# mainboard.net
KiCad netlist of a schematic drawn in EAGLE
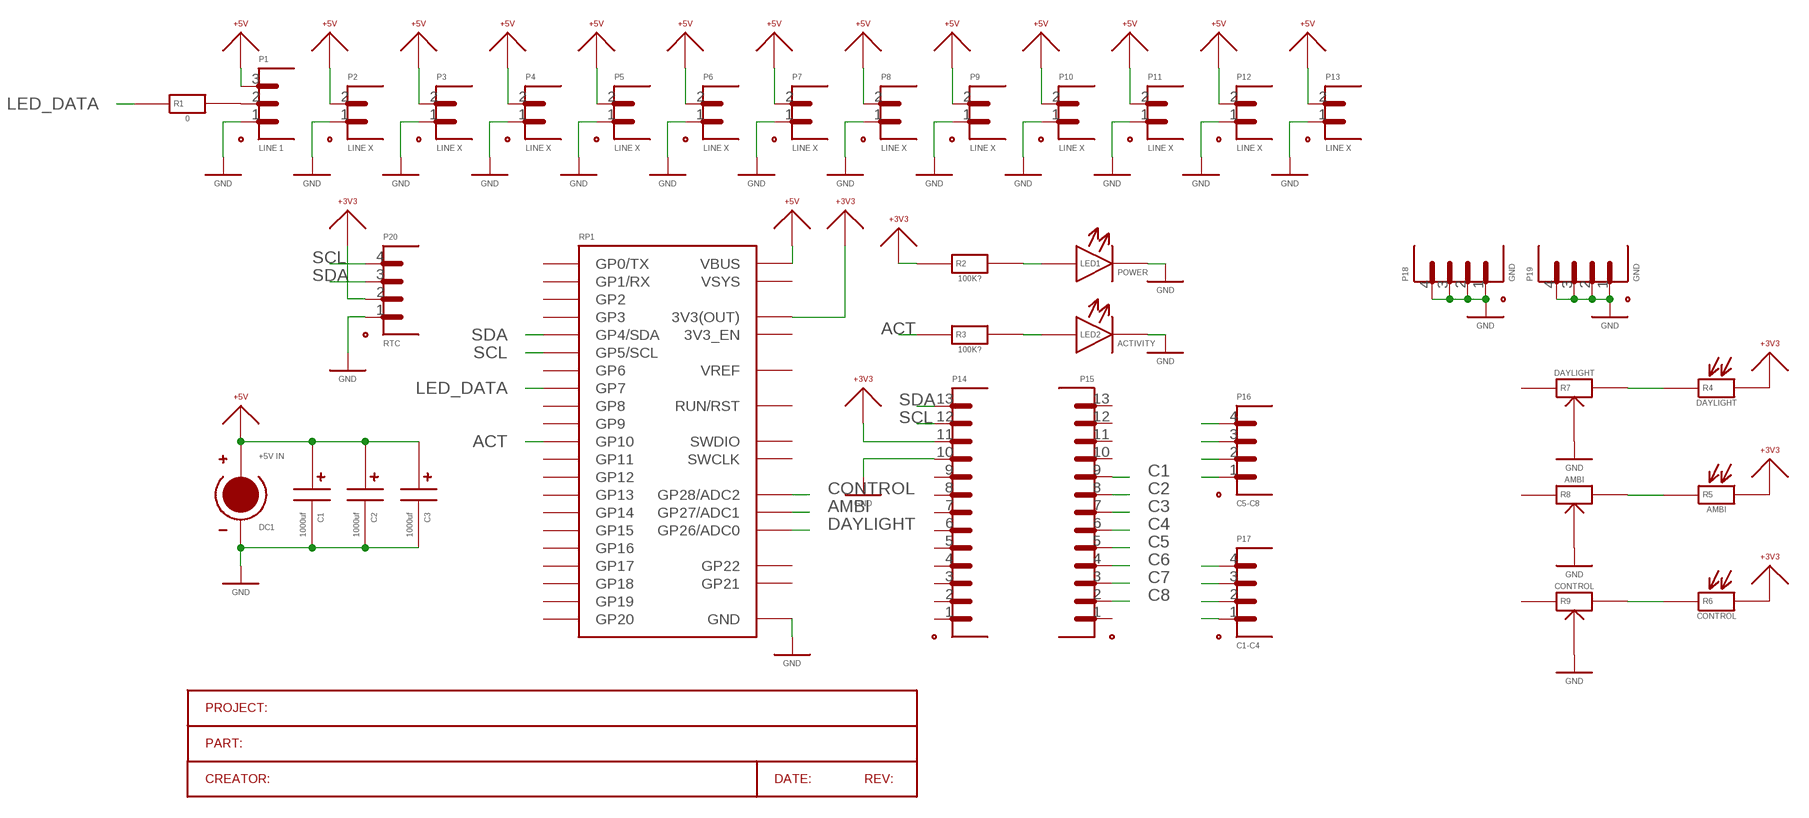
[diagram p0: schematic, sheet 1]

(export (version "E")
  (design (tool "Eeschema 10.0.6"))
  (components
    (comp (ref "C1")
      (value "1000uf")
      (footprint "eagle-import:CAPACITOR_POLAR_8MM")
      (libsource (lib "eagle-import") (part "CAPACITOR_POLARISED_8MM"))
    )
    (comp (ref "C2")
      (value "1000uf")
      (footprint "eagle-import:CAPACITOR_POLAR_8MM")
      (libsource (lib "eagle-import") (part "CAPACITOR_POLARISED_8MM"))
    )
    (comp (ref "C3")
      (value "1000uf")
      (footprint "eagle-import:CAPACITOR_POLAR_8MM")
      (libsource (lib "eagle-import") (part "CAPACITOR_POLARISED_8MM"))
    )
    (comp (ref "DC1")
      (value "+5V IN")
      (footprint "eagle-import:SCREW-TERMINAL_2-WAY")
      (libsource (lib "eagle-import") (part "DC-POWER_SCREW-TERMINAL"))
    )
    (comp (ref "LED1")
      (value "POWER")
      (footprint "eagle-import:LED_3MM")
      (libsource (lib "eagle-import") (part "LED_3MM"))
    )
    (comp (ref "LED2")
      (value "ACTIVITY")
      (footprint "eagle-import:LED_3MM")
      (libsource (lib "eagle-import") (part "LED_3MM"))
    )
    (comp (ref "P1")
      (value "LINE 1")
      (footprint "eagle-import:SCREW-TERMINAL_3-WAY")
      (libsource (lib "eagle-import") (part "PORT_3-PIN_SCREW-TERMINAL"))
    )
    (comp (ref "P2")
      (value "LINE X")
      (footprint "eagle-import:SCREW-TERMINAL_2-WAY")
      (libsource (lib "eagle-import") (part "PORT_2-PIN_SCREW-TERMINAL"))
    )
    (comp (ref "P3")
      (value "LINE X")
      (footprint "eagle-import:SCREW-TERMINAL_2-WAY")
      (libsource (lib "eagle-import") (part "PORT_2-PIN_SCREW-TERMINAL"))
    )
    (comp (ref "P4")
      (value "LINE X")
      (footprint "eagle-import:SCREW-TERMINAL_2-WAY")
      (libsource (lib "eagle-import") (part "PORT_2-PIN_SCREW-TERMINAL"))
    )
    (comp (ref "P5")
      (value "LINE X")
      (footprint "eagle-import:SCREW-TERMINAL_2-WAY")
      (libsource (lib "eagle-import") (part "PORT_2-PIN_SCREW-TERMINAL"))
    )
    (comp (ref "P6")
      (value "LINE X")
      (footprint "eagle-import:SCREW-TERMINAL_2-WAY")
      (libsource (lib "eagle-import") (part "PORT_2-PIN_SCREW-TERMINAL"))
    )
    (comp (ref "P7")
      (value "LINE X")
      (footprint "eagle-import:SCREW-TERMINAL_2-WAY")
      (libsource (lib "eagle-import") (part "PORT_2-PIN_SCREW-TERMINAL"))
    )
    (comp (ref "P8")
      (value "LINE X")
      (footprint "eagle-import:SCREW-TERMINAL_2-WAY")
      (libsource (lib "eagle-import") (part "PORT_2-PIN_SCREW-TERMINAL"))
    )
    (comp (ref "P9")
      (value "LINE X")
      (footprint "eagle-import:SCREW-TERMINAL_2-WAY")
      (libsource (lib "eagle-import") (part "PORT_2-PIN_SCREW-TERMINAL"))
    )
    (comp (ref "P10")
      (value "LINE X")
      (footprint "eagle-import:SCREW-TERMINAL_2-WAY")
      (libsource (lib "eagle-import") (part "PORT_2-PIN_SCREW-TERMINAL"))
    )
    (comp (ref "P11")
      (value "LINE X")
      (footprint "eagle-import:SCREW-TERMINAL_2-WAY")
      (libsource (lib "eagle-import") (part "PORT_2-PIN_SCREW-TERMINAL"))
    )
    (comp (ref "P12")
      (value "LINE X")
      (footprint "eagle-import:SCREW-TERMINAL_2-WAY")
      (libsource (lib "eagle-import") (part "PORT_2-PIN_SCREW-TERMINAL"))
    )
    (comp (ref "P13")
      (value "LINE X")
      (footprint "eagle-import:SCREW-TERMINAL_2-WAY")
      (libsource (lib "eagle-import") (part "PORT_2-PIN_SCREW-TERMINAL"))
    )
    (comp (ref "P14")
      (value "PORT_13-PIN_HEADER")
      (footprint "eagle-import:HEADER_13-PIN")
      (libsource (lib "eagle-import") (part "PORT_13-PIN_HEADER"))
    )
    (comp (ref "P15")
      (value "PORT_13-PIN_HEADER")
      (footprint "eagle-import:HEADER_13-PIN")
      (libsource (lib "eagle-import") (part "PORT_13-PIN_HEADER"))
    )
    (comp (ref "P16")
      (value "C5-C8")
      (footprint "eagle-import:R5210_4-PIN")
      (libsource (lib "eagle-import") (part "PORT_4-PIN_R5210"))
    )
    (comp (ref "P17")
      (value "C1-C4")
      (footprint "eagle-import:R5210_4-PIN")
      (libsource (lib "eagle-import") (part "PORT_4-PIN_R5210"))
    )
    (comp (ref "P18")
      (value "GND")
      (footprint "eagle-import:R5210_4-PIN")
      (libsource (lib "eagle-import") (part "PORT_4-PIN_R5210"))
    )
    (comp (ref "P19")
      (value "GND")
      (footprint "eagle-import:R5210_4-PIN")
      (libsource (lib "eagle-import") (part "PORT_4-PIN_R5210"))
    )
    (comp (ref "P20")
      (value "RTC")
      (footprint "eagle-import:R5210_4-PIN")
      (libsource (lib "eagle-import") (part "PORT_4-PIN_R5210"))
    )
    (comp (ref "R1")
      (value "0")
      (footprint "eagle-import:RESISTOR_10.16MM")
      (libsource (lib "eagle-import") (part "RESISTOR_10.16MM"))
    )
    (comp (ref "R2")
      (value "100K?")
      (footprint "eagle-import:RESISTOR_10.16MM")
      (libsource (lib "eagle-import") (part "RESISTOR_10.16MM"))
    )
    (comp (ref "R3")
      (value "100K?")
      (footprint "eagle-import:RESISTOR_10.16MM")
      (libsource (lib "eagle-import") (part "RESISTOR_10.16MM"))
    )
    (comp (ref "R4")
      (value "DAYLIGHT")
      (footprint "eagle-import:R5210_2-PIN")
      (libsource (lib "eagle-import") (part "RESISTOR_LRD_R5210"))
    )
    (comp (ref "R5")
      (value "AMBI")
      (footprint "eagle-import:PASSIVE_2.54MM")
      (libsource (lib "eagle-import") (part "RESISTOR_LRD_2.54MM"))
    )
    (comp (ref "R6")
      (value "CONTROL")
      (footprint "eagle-import:PASSIVE_2.54MM")
      (libsource (lib "eagle-import") (part "RESISTOR_LRD_2.54MM"))
    )
    (comp (ref "R7")
      (value "DAYLIGHT")
      (footprint "eagle-import:TRIM-POT_A")
      (libsource (lib "eagle-import") (part "RESISTOR_VARIABLE_TRIM-POT"))
    )
    (comp (ref "R8")
      (value "AMBI")
      (footprint "eagle-import:TRIM-POT_A")
      (libsource (lib "eagle-import") (part "RESISTOR_VARIABLE_TRIM-POT"))
    )
    (comp (ref "R9")
      (value "CONTROL")
      (footprint "eagle-import:TRIM-POT_A")
      (libsource (lib "eagle-import") (part "RESISTOR_VARIABLE_TRIM-POT"))
    )
    (comp (ref "RP1")
      (value "RASPBERRY-PI-PICO_W")
      (footprint "eagle-import:RASPBERRY-PI-PICO_W")
      (libsource (lib "eagle-import") (part "RASPBERRY-PI-PICO_W"))
    )
  )
  (nets
    (net (code "1") (name "+3V3") (class "Default")
      (node (ref "P14") (pin "11") (pinfunction "11_11") (pintype "bidirectional"))
      (node (ref "P20") (pin "2") (pinfunction "2_2") (pintype "bidirectional"))
      (node (ref "R2") (pin "X") (pinfunction "X_X") (pintype "passive"))
      (node (ref "R4") (pin "2") (pinfunction "Y_2") (pintype "passive"))
      (node (ref "R5") (pin "Y") (pinfunction "Y_Y") (pintype "passive"))
      (node (ref "R6") (pin "Y") (pinfunction "Y_Y") (pintype "passive"))
      (node (ref "RP1") (pin "36") (pinfunction "3V3(OUT)_36") (pintype "power_in"))
    )
    (net (code "2") (name "+5V") (class "Default")
      (node (ref "C1") (pin "A") (pinfunction "A_A") (pintype "input"))
      (node (ref "C2") (pin "A") (pinfunction "A_A") (pintype "input"))
      (node (ref "C3") (pin "A") (pinfunction "A_A") (pintype "input"))
      (node (ref "DC1") (pin "2") (pinfunction "+V_2") (pintype "power_in"))
      (node (ref "P1") (pin "3") (pinfunction "3_3") (pintype "bidirectional"))
      (node (ref "P10") (pin "2") (pinfunction "2_2") (pintype "bidirectional"))
      (node (ref "P11") (pin "2") (pinfunction "2_2") (pintype "bidirectional"))
      (node (ref "P12") (pin "2") (pinfunction "2_2") (pintype "bidirectional"))
      (node (ref "P13") (pin "2") (pinfunction "2_2") (pintype "bidirectional"))
      (node (ref "P2") (pin "2") (pinfunction "2_2") (pintype "bidirectional"))
      (node (ref "P3") (pin "2") (pinfunction "2_2") (pintype "bidirectional"))
      (node (ref "P4") (pin "2") (pinfunction "2_2") (pintype "bidirectional"))
      (node (ref "P5") (pin "2") (pinfunction "2_2") (pintype "bidirectional"))
      (node (ref "P6") (pin "2") (pinfunction "2_2") (pintype "bidirectional"))
      (node (ref "P7") (pin "2") (pinfunction "2_2") (pintype "bidirectional"))
      (node (ref "P8") (pin "2") (pinfunction "2_2") (pintype "bidirectional"))
      (node (ref "P9") (pin "2") (pinfunction "2_2") (pintype "bidirectional"))
      (node (ref "RP1") (pin "40") (pinfunction "VBUS_40") (pintype "power_in"))
    )
    (net (code "3") (name "/ACT") (class "Default")
      (node (ref "R3") (pin "X") (pinfunction "X_X") (pintype "passive"))
      (node (ref "RP1") (pin "14") (pinfunction "GP10_14") (pintype "bidirectional"))
    )
    (net (code "4") (name "/AMBI") (class "Default")
      (node (ref "R5") (pin "X") (pinfunction "X_X") (pintype "passive"))
      (node (ref "R8") (pin "Y") (pinfunction "Y_Y") (pintype "passive"))
      (node (ref "RP1") (pin "32") (pinfunction "GP27/ADC1_32") (pintype "bidirectional"))
    )
    (net (code "5") (name "/C1") (class "Default")
      (node (ref "P15") (pin "9") (pinfunction "9_9") (pintype "bidirectional"))
      (node (ref "P17") (pin "1") (pinfunction "1_1") (pintype "bidirectional"))
    )
    (net (code "6") (name "/C2") (class "Default")
      (node (ref "P15") (pin "8") (pinfunction "8_8") (pintype "bidirectional"))
      (node (ref "P17") (pin "2") (pinfunction "2_2") (pintype "bidirectional"))
    )
    (net (code "7") (name "/C3") (class "Default")
      (node (ref "P15") (pin "7") (pinfunction "7_7") (pintype "bidirectional"))
      (node (ref "P17") (pin "3") (pinfunction "3_3") (pintype "bidirectional"))
    )
    (net (code "8") (name "/C4") (class "Default")
      (node (ref "P15") (pin "6") (pinfunction "6_6") (pintype "bidirectional"))
      (node (ref "P17") (pin "4") (pinfunction "4_4") (pintype "bidirectional"))
    )
    (net (code "9") (name "/C5") (class "Default")
      (node (ref "P15") (pin "5") (pinfunction "5_5") (pintype "bidirectional"))
      (node (ref "P16") (pin "1") (pinfunction "1_1") (pintype "bidirectional"))
    )
    (net (code "10") (name "/C6") (class "Default")
      (node (ref "P15") (pin "4") (pinfunction "4_4") (pintype "bidirectional"))
      (node (ref "P16") (pin "2") (pinfunction "2_2") (pintype "bidirectional"))
    )
    (net (code "11") (name "/C7") (class "Default")
      (node (ref "P15") (pin "3") (pinfunction "3_3") (pintype "bidirectional"))
      (node (ref "P16") (pin "3") (pinfunction "3_3") (pintype "bidirectional"))
    )
    (net (code "12") (name "/C8") (class "Default")
      (node (ref "P15") (pin "2") (pinfunction "2_2") (pintype "bidirectional"))
      (node (ref "P16") (pin "4") (pinfunction "4_4") (pintype "bidirectional"))
    )
    (net (code "13") (name "/CONTROL") (class "Default")
      (node (ref "R6") (pin "X") (pinfunction "X_X") (pintype "passive"))
      (node (ref "R9") (pin "Y") (pinfunction "Y_Y") (pintype "passive"))
      (node (ref "RP1") (pin "34") (pinfunction "GP28/ADC2_34") (pintype "bidirectional"))
    )
    (net (code "14") (name "/DAYLIGHT") (class "Default")
      (node (ref "R4") (pin "1") (pinfunction "X_1") (pintype "passive"))
      (node (ref "R7") (pin "Y") (pinfunction "Y_Y") (pintype "passive"))
      (node (ref "RP1") (pin "31") (pinfunction "GP26/ADC0_31") (pintype "bidirectional"))
    )
    (net (code "15") (name "/LED_DATA") (class "Default")
      (node (ref "R1") (pin "X") (pinfunction "X_X") (pintype "passive"))
      (node (ref "RP1") (pin "10") (pinfunction "GP7_10") (pintype "bidirectional"))
    )
    (net (code "16") (name "/SCL") (class "Default")
      (node (ref "P14") (pin "12") (pinfunction "12_12") (pintype "bidirectional"))
      (node (ref "P20") (pin "4") (pinfunction "4_4") (pintype "bidirectional"))
      (node (ref "RP1") (pin "7") (pinfunction "GP5/SCL_7") (pintype "bidirectional"))
    )
    (net (code "17") (name "/SDA") (class "Default")
      (node (ref "P14") (pin "13") (pinfunction "13_13") (pintype "bidirectional"))
      (node (ref "P20") (pin "3") (pinfunction "3_3") (pintype "bidirectional"))
      (node (ref "RP1") (pin "6") (pinfunction "GP4/SDA_6") (pintype "bidirectional"))
    )
    (net (code "18") (name "/VSYS") (class "Default")
      (node (ref "RP1") (pin "39") (pinfunction "VSYS_39") (pintype "power_in"))
    )
    (net (code "19") (name "GND") (class "Default")
      (node (ref "C1") (pin "C") (pinfunction "C_C") (pintype "output"))
      (node (ref "C2") (pin "C") (pinfunction "C_C") (pintype "output"))
      (node (ref "C3") (pin "C") (pinfunction "C_C") (pintype "output"))
      (node (ref "DC1") (pin "1") (pinfunction "-V_1") (pintype "power_in"))
      (node (ref "LED1") (pin "C") (pinfunction "C_C") (pintype "output"))
      (node (ref "LED2") (pin "C") (pinfunction "C_C") (pintype "output"))
      (node (ref "P1") (pin "1") (pinfunction "1_1") (pintype "bidirectional"))
      (node (ref "P10") (pin "1") (pinfunction "1_1") (pintype "bidirectional"))
      (node (ref "P11") (pin "1") (pinfunction "1_1") (pintype "bidirectional"))
      (node (ref "P12") (pin "1") (pinfunction "1_1") (pintype "bidirectional"))
      (node (ref "P13") (pin "1") (pinfunction "1_1") (pintype "bidirectional"))
      (node (ref "P14") (pin "10") (pinfunction "10_10") (pintype "bidirectional"))
      (node (ref "P18") (pin "1") (pinfunction "1_1") (pintype "bidirectional"))
      (node (ref "P18") (pin "2") (pinfunction "2_2") (pintype "bidirectional"))
      (node (ref "P18") (pin "3") (pinfunction "3_3") (pintype "bidirectional"))
      (node (ref "P18") (pin "4") (pinfunction "4_4") (pintype "bidirectional"))
      (node (ref "P19") (pin "1") (pinfunction "1_1") (pintype "bidirectional"))
      (node (ref "P19") (pin "2") (pinfunction "2_2") (pintype "bidirectional"))
      (node (ref "P19") (pin "3") (pinfunction "3_3") (pintype "bidirectional"))
      (node (ref "P19") (pin "4") (pinfunction "4_4") (pintype "bidirectional"))
      (node (ref "P2") (pin "1") (pinfunction "1_1") (pintype "bidirectional"))
      (node (ref "P20") (pin "1") (pinfunction "1_1") (pintype "bidirectional"))
      (node (ref "P3") (pin "1") (pinfunction "1_1") (pintype "bidirectional"))
      (node (ref "P4") (pin "1") (pinfunction "1_1") (pintype "bidirectional"))
      (node (ref "P5") (pin "1") (pinfunction "1_1") (pintype "bidirectional"))
      (node (ref "P6") (pin "1") (pinfunction "1_1") (pintype "bidirectional"))
      (node (ref "P7") (pin "1") (pinfunction "1_1") (pintype "bidirectional"))
      (node (ref "P8") (pin "1") (pinfunction "1_1") (pintype "bidirectional"))
      (node (ref "P9") (pin "1") (pinfunction "1_1") (pintype "bidirectional"))
      (node (ref "R7") (pin "1") (pinfunction "1_1") (pintype "passive"))
      (node (ref "R8") (pin "1") (pinfunction "1_1") (pintype "passive"))
      (node (ref "R9") (pin "1") (pinfunction "1_1") (pintype "passive"))
      (node (ref "RP1") (pin "13") (pinfunction "GND_13") (pintype "power_in"))
      (node (ref "RP1") (pin "18") (pinfunction "GND_18") (pintype "power_in"))
      (node (ref "RP1") (pin "23") (pinfunction "GND_23") (pintype "power_in"))
      (node (ref "RP1") (pin "28") (pinfunction "GND_28") (pintype "power_in"))
      (node (ref "RP1") (pin "3") (pinfunction "GND_3") (pintype "power_in"))
      (node (ref "RP1") (pin "33") (pinfunction "GND_33") (pintype "power_in"))
      (node (ref "RP1") (pin "38") (pinfunction "GND_38") (pintype "power_in"))
      (node (ref "RP1") (pin "8") (pinfunction "GND_8") (pintype "power_in"))
      (node (ref "RP1") (pin "D_GND") (pinfunction "GND_D_GND") (pintype "power_in"))
    )
    (net (code "20") (name "Net-(LED1-PadA)") (class "Default")
      (node (ref "LED1") (pin "A") (pinfunction "A_A") (pintype "input"))
      (node (ref "R2") (pin "Y") (pinfunction "Y_Y") (pintype "passive"))
    )
    (net (code "21") (name "Net-(LED2-PadA)") (class "Default")
      (node (ref "LED2") (pin "A") (pinfunction "A_A") (pintype "input"))
      (node (ref "R3") (pin "Y") (pinfunction "Y_Y") (pintype "passive"))
    )
    (net (code "22") (name "Net-(P1-Pad2)") (class "Default")
      (node (ref "P1") (pin "2") (pinfunction "2_2") (pintype "bidirectional"))
      (node (ref "R1") (pin "Y") (pinfunction "Y_Y") (pintype "passive"))
    )
    (net (code "23") (name "unconnected-(P14-Pad1)") (class "Default")
      (node (ref "P14") (pin "1") (pinfunction "1_1") (pintype "bidirectional"))
    )
    (net (code "24") (name "unconnected-(P14-Pad2)") (class "Default")
      (node (ref "P14") (pin "2") (pinfunction "2_2") (pintype "bidirectional"))
    )
    (net (code "25") (name "unconnected-(P14-Pad3)") (class "Default")
      (node (ref "P14") (pin "3") (pinfunction "3_3") (pintype "bidirectional"))
    )
    (net (code "26") (name "unconnected-(P14-Pad4)") (class "Default")
      (node (ref "P14") (pin "4") (pinfunction "4_4") (pintype "bidirectional"))
    )
    (net (code "27") (name "unconnected-(P14-Pad5)") (class "Default")
      (node (ref "P14") (pin "5") (pinfunction "5_5") (pintype "bidirectional"))
    )
    (net (code "28") (name "unconnected-(P14-Pad6)") (class "Default")
      (node (ref "P14") (pin "6") (pinfunction "6_6") (pintype "bidirectional"))
    )
    (net (code "29") (name "unconnected-(P14-Pad7)") (class "Default")
      (node (ref "P14") (pin "7") (pinfunction "7_7") (pintype "bidirectional"))
    )
    (net (code "30") (name "unconnected-(P14-Pad8)") (class "Default")
      (node (ref "P14") (pin "8") (pinfunction "8_8") (pintype "bidirectional"))
    )
    (net (code "31") (name "unconnected-(P14-Pad9)") (class "Default")
      (node (ref "P14") (pin "9") (pinfunction "9_9") (pintype "bidirectional"))
    )
    (net (code "32") (name "unconnected-(P15-Pad1)") (class "Default")
      (node (ref "P15") (pin "1") (pinfunction "1_1") (pintype "bidirectional"))
    )
    (net (code "33") (name "unconnected-(P15-Pad10)") (class "Default")
      (node (ref "P15") (pin "10") (pinfunction "10_10") (pintype "bidirectional"))
    )
    (net (code "34") (name "unconnected-(P15-Pad11)") (class "Default")
      (node (ref "P15") (pin "11") (pinfunction "11_11") (pintype "bidirectional"))
    )
    (net (code "35") (name "unconnected-(P15-Pad12)") (class "Default")
      (node (ref "P15") (pin "12") (pinfunction "12_12") (pintype "bidirectional"))
    )
    (net (code "36") (name "unconnected-(P15-Pad13)") (class "Default")
      (node (ref "P15") (pin "13") (pinfunction "13_13") (pintype "bidirectional"))
    )
    (net (code "37") (name "unconnected-(R7-PadX)") (class "Default")
      (node (ref "R7") (pin "X") (pinfunction "X_X") (pintype "passive"))
    )
    (net (code "38") (name "unconnected-(R8-PadX)") (class "Default")
      (node (ref "R8") (pin "X") (pinfunction "X_X") (pintype "passive"))
    )
    (net (code "39") (name "unconnected-(R9-PadX)") (class "Default")
      (node (ref "R9") (pin "X") (pinfunction "X_X") (pintype "passive"))
    )
    (net (code "40") (name "unconnected-(RP1-3V3_EN-Pad37)") (class "Default")
      (node (ref "RP1") (pin "37") (pinfunction "3V3_EN_37") (pintype "bidirectional"))
    )
    (net (code "41") (name "unconnected-(RP1-GP0{slash}TX-Pad1)") (class "Default")
      (node (ref "RP1") (pin "1") (pinfunction "GP0/TX_1") (pintype "bidirectional"))
    )
    (net (code "42") (name "unconnected-(RP1-GP1{slash}RX-Pad2)") (class "Default")
      (node (ref "RP1") (pin "2") (pinfunction "GP1/RX_2") (pintype "bidirectional"))
    )
    (net (code "43") (name "unconnected-(RP1-GP2-Pad4)") (class "Default")
      (node (ref "RP1") (pin "4") (pinfunction "GP2_4") (pintype "bidirectional"))
    )
    (net (code "44") (name "unconnected-(RP1-GP3-Pad5)") (class "Default")
      (node (ref "RP1") (pin "5") (pinfunction "GP3_5") (pintype "bidirectional"))
    )
    (net (code "45") (name "unconnected-(RP1-GP6-Pad9)") (class "Default")
      (node (ref "RP1") (pin "9") (pinfunction "GP6_9") (pintype "bidirectional"))
    )
    (net (code "46") (name "unconnected-(RP1-GP8-Pad11)") (class "Default")
      (node (ref "RP1") (pin "11") (pinfunction "GP8_11") (pintype "bidirectional"))
    )
    (net (code "47") (name "unconnected-(RP1-GP9-Pad12)") (class "Default")
      (node (ref "RP1") (pin "12") (pinfunction "GP9_12") (pintype "bidirectional"))
    )
    (net (code "48") (name "unconnected-(RP1-GP11-Pad15)") (class "Default")
      (node (ref "RP1") (pin "15") (pinfunction "GP11_15") (pintype "bidirectional"))
    )
    (net (code "49") (name "unconnected-(RP1-GP12-Pad16)") (class "Default")
      (node (ref "RP1") (pin "16") (pinfunction "GP12_16") (pintype "bidirectional"))
    )
    (net (code "50") (name "unconnected-(RP1-GP13-Pad17)") (class "Default")
      (node (ref "RP1") (pin "17") (pinfunction "GP13_17") (pintype "bidirectional"))
    )
    (net (code "51") (name "unconnected-(RP1-GP14-Pad19)") (class "Default")
      (node (ref "RP1") (pin "19") (pinfunction "GP14_19") (pintype "bidirectional"))
    )
    (net (code "52") (name "unconnected-(RP1-GP15-Pad20)") (class "Default")
      (node (ref "RP1") (pin "20") (pinfunction "GP15_20") (pintype "bidirectional"))
    )
    (net (code "53") (name "unconnected-(RP1-GP16-Pad21)") (class "Default")
      (node (ref "RP1") (pin "21") (pinfunction "GP16_21") (pintype "bidirectional"))
    )
    (net (code "54") (name "unconnected-(RP1-GP17-Pad22)") (class "Default")
      (node (ref "RP1") (pin "22") (pinfunction "GP17_22") (pintype "bidirectional"))
    )
    (net (code "55") (name "unconnected-(RP1-GP18-Pad24)") (class "Default")
      (node (ref "RP1") (pin "24") (pinfunction "GP18_24") (pintype "bidirectional"))
    )
    (net (code "56") (name "unconnected-(RP1-GP19-Pad25)") (class "Default")
      (node (ref "RP1") (pin "25") (pinfunction "GP19_25") (pintype "bidirectional"))
    )
    (net (code "57") (name "unconnected-(RP1-GP20-Pad26)") (class "Default")
      (node (ref "RP1") (pin "26") (pinfunction "GP20_26") (pintype "bidirectional"))
    )
    (net (code "58") (name "unconnected-(RP1-GP21-Pad27)") (class "Default")
      (node (ref "RP1") (pin "27") (pinfunction "GP21_27") (pintype "bidirectional"))
    )
    (net (code "59") (name "unconnected-(RP1-GP22-Pad29)") (class "Default")
      (node (ref "RP1") (pin "29") (pinfunction "GP22_29") (pintype "bidirectional"))
    )
    (net (code "60") (name "unconnected-(RP1-PadSWCLK)") (class "Default")
      (node (ref "RP1") (pin "SWCLK") (pinfunction "SWCLK_SWCLK") (pintype "bidirectional"))
    )
    (net (code "61") (name "unconnected-(RP1-PadSWDIO)") (class "Default")
      (node (ref "RP1") (pin "SWDIO") (pinfunction "SWDIO_SWDIO") (pintype "bidirectional"))
    )
    (net (code "62") (name "unconnected-(RP1-RUN{slash}RST-Pad30)") (class "Default")
      (node (ref "RP1") (pin "30") (pinfunction "RUN/RST_30") (pintype "bidirectional"))
    )
    (net (code "63") (name "unconnected-(RP1-VREF-Pad35)") (class "Default")
      (node (ref "RP1") (pin "35") (pinfunction "VREF_35") (pintype "bidirectional"))
    )
  )
)
